# IMU_Sensor.net
KiCad netlist of a schematic drawn in Altium Designer
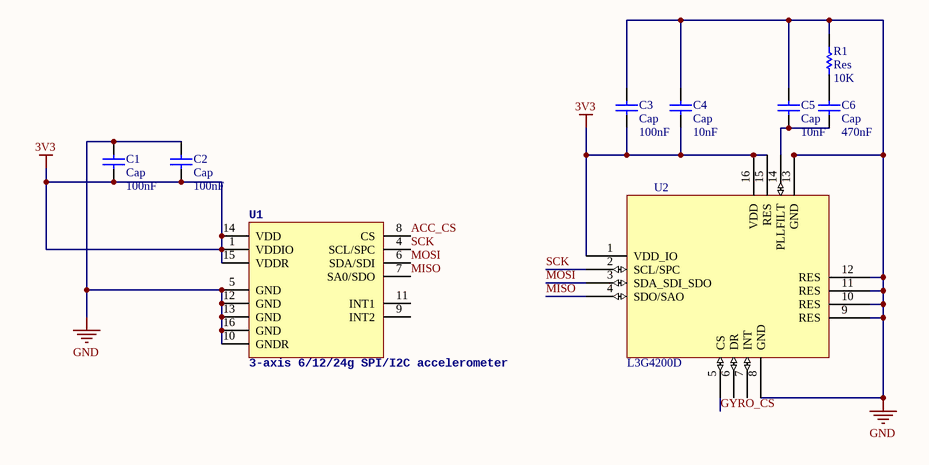
[diagram p0: IMU Sensor.SchDoc]

(export (version "E")
  (design (tool "Eeschema 10.0.6"))
  (components
    (comp (ref "C1")
      (value "Cap")
      (footprint "0603-CAP")
      (description "Capacitor")
      (fields (field (name "ALTIUM_VALUE") "100nF") (field (name "PUBLISHER") "Altium Limited"))
      (libsource (lib "BarelangRobotics") (part "Cap"))
    )
    (comp (ref "C2")
      (value "Cap")
      (footprint "0603-CAP")
      (description "Capacitor")
      (fields (field (name "ALTIUM_VALUE") "100nF") (field (name "PUBLISHER") "Altium Limited"))
      (libsource (lib "BarelangRobotics") (part "Cap"))
    )
    (comp (ref "C3")
      (value "Cap")
      (footprint "0603-CAP")
      (description "Capacitor")
      (fields (field (name "ALTIUM_VALUE") "100nF") (field (name "PUBLISHER") "Altium Limited"))
      (libsource (lib "BarelangRobotics") (part "Cap"))
    )
    (comp (ref "C4")
      (value "Cap")
      (footprint "0603-CAP")
      (description "Capacitor")
      (fields (field (name "ALTIUM_VALUE") "10nF") (field (name "PUBLISHER") "Altium Limited"))
      (libsource (lib "BarelangRobotics") (part "Cap"))
    )
    (comp (ref "C5")
      (value "Cap")
      (footprint "0603-CAP")
      (description "Capacitor")
      (fields (field (name "ALTIUM_VALUE") "10nF") (field (name "PUBLISHER") "Altium Limited"))
      (libsource (lib "BarelangRobotics") (part "Cap"))
    )
    (comp (ref "C6")
      (value "Cap")
      (footprint "0603-CAP")
      (description "Capacitor")
      (fields (field (name "ALTIUM_VALUE") "470nF") (field (name "PUBLISHER") "Altium Limited"))
      (libsource (lib "BarelangRobotics") (part "Cap"))
    )
    (comp (ref "R1")
      (value "Res")
      (footprint "0603-RES")
      (description "Resistor")
      (fields (field (name "ALTIUM_VALUE") "10K") (field (name "PUBLISHER") "Altium Limited"))
      (libsource (lib "BarelangRobotics") (part "Res"))
    )
    (comp (ref "U1")
      (value "3-axis 6/12/24g SPI/I2C accelerometer")
      (footprint "LGA16-3MM")
      (libsource (lib "BarelangRobotics") (part "LIS331"))
    )
    (comp (ref "U2")
      (value "L3G4200D")
      (footprint "L3G4200D")
      (libsource (lib "BRCM-Additional-Library") (part "L3G4200D"))
    )
  )
  (nets
    (net (code "1") (name "/ACC_CS") (class "Default")
      (node (ref "U1") (pin "8") (pinfunction "CS_8") (pintype "passive"))
    )
    (net (code "2") (name "/GYRO_CS") (class "Default")
      (node (ref "U2") (pin "5") (pinfunction "CS_5") (pintype "bidirectional"))
    )
    (net (code "3") (name "/MISO") (class "Default")
      (node (ref "U1") (pin "7") (pinfunction "SA0/SDO_7") (pintype "passive"))
      (node (ref "U2") (pin "4") (pinfunction "SDO/SAO_4") (pintype "bidirectional"))
    )
    (net (code "4") (name "/MOSI") (class "Default")
      (node (ref "U1") (pin "6") (pinfunction "SDA/SDI_6") (pintype "passive"))
      (node (ref "U2") (pin "3") (pinfunction "SDA_SDI_SDO_3") (pintype "bidirectional"))
    )
    (net (code "5") (name "/SCK") (class "Default")
      (node (ref "U1") (pin "4") (pinfunction "SCL/SPC_4") (pintype "passive"))
      (node (ref "U2") (pin "2") (pinfunction "SCL/SPC_2") (pintype "bidirectional"))
    )
    (net (code "6") (name "3V3") (class "Default")
      (node (ref "C1") (pin "1") (pinfunction "1_1") (pintype "passive"))
      (node (ref "C2") (pin "1") (pinfunction "1_1") (pintype "passive"))
      (node (ref "C3") (pin "1") (pinfunction "1_1") (pintype "passive"))
      (node (ref "C4") (pin "1") (pinfunction "1_1") (pintype "passive"))
      (node (ref "U1") (pin "1") (pinfunction "VDDIO_1") (pintype "passive"))
      (node (ref "U1") (pin "14") (pinfunction "VDD_14") (pintype "passive"))
      (node (ref "U1") (pin "15") (pinfunction "VDDR_15") (pintype "passive"))
      (node (ref "U2") (pin "1") (pinfunction "VDD_IO_1") (pintype "power_in"))
      (node (ref "U2") (pin "15") (pinfunction "RES_15") (pintype "power_in"))
      (node (ref "U2") (pin "16") (pinfunction "VDD_16") (pintype "power_in"))
    )
    (net (code "7") (name "GND") (class "Default")
      (node (ref "C1") (pin "2") (pinfunction "2_2") (pintype "passive"))
      (node (ref "C2") (pin "2") (pinfunction "2_2") (pintype "passive"))
      (node (ref "C3") (pin "2") (pinfunction "2_2") (pintype "passive"))
      (node (ref "C4") (pin "2") (pinfunction "2_2") (pintype "passive"))
      (node (ref "C5") (pin "1") (pinfunction "1_1") (pintype "passive"))
      (node (ref "R1") (pin "2") (pinfunction "2_2") (pintype "passive"))
      (node (ref "U1") (pin "10") (pinfunction "GNDR_10") (pintype "passive"))
      (node (ref "U1") (pin "12") (pinfunction "GND_12") (pintype "passive"))
      (node (ref "U1") (pin "13") (pinfunction "GND_13") (pintype "passive"))
      (node (ref "U1") (pin "16") (pinfunction "GND_16") (pintype "passive"))
      (node (ref "U1") (pin "5") (pinfunction "GND_5") (pintype "passive"))
      (node (ref "U2") (pin "10") (pinfunction "RES_10") (pintype "power_in"))
      (node (ref "U2") (pin "11") (pinfunction "RES_11") (pintype "power_in"))
      (node (ref "U2") (pin "12") (pinfunction "RES_12") (pintype "power_in"))
      (node (ref "U2") (pin "13") (pinfunction "GND_13") (pintype "power_in"))
      (node (ref "U2") (pin "8") (pinfunction "GND_8") (pintype "power_in"))
      (node (ref "U2") (pin "9") (pinfunction "RES_9") (pintype "power_in"))
    )
    (net (code "8") (name "Net-(C6-Pad2)") (class "Default")
      (node (ref "C6") (pin "2") (pinfunction "2_2") (pintype "passive"))
      (node (ref "R1") (pin "1") (pinfunction "1_1") (pintype "passive"))
    )
    (net (code "9") (name "Net-(U2-PLLFILT)") (class "Default")
      (node (ref "C5") (pin "2") (pinfunction "2_2") (pintype "passive"))
      (node (ref "C6") (pin "1") (pinfunction "1_1") (pintype "passive"))
      (node (ref "U2") (pin "14") (pinfunction "PLLFILT_14") (pintype "bidirectional"))
    )
    (net (code "10") (name "unconnected-(U1-INT1-Pad11)") (class "Default")
      (node (ref "U1") (pin "11") (pinfunction "INT1_11") (pintype "passive"))
    )
    (net (code "11") (name "unconnected-(U1-INT2-Pad9)") (class "Default")
      (node (ref "U1") (pin "9") (pinfunction "INT2_9") (pintype "passive"))
    )
    (net (code "12") (name "unconnected-(U2-DR-Pad6)") (class "Default")
      (node (ref "U2") (pin "6") (pinfunction "DR_6") (pintype "bidirectional"))
    )
    (net (code "13") (name "unconnected-(U2-INT-Pad7)") (class "Default")
      (node (ref "U2") (pin "7") (pinfunction "INT_7") (pintype "bidirectional"))
    )
  )
)
